# SCH_Sentinel-Controller-board_2025-03-25.net
KiCad netlist of a schematic drawn in EasyEDA
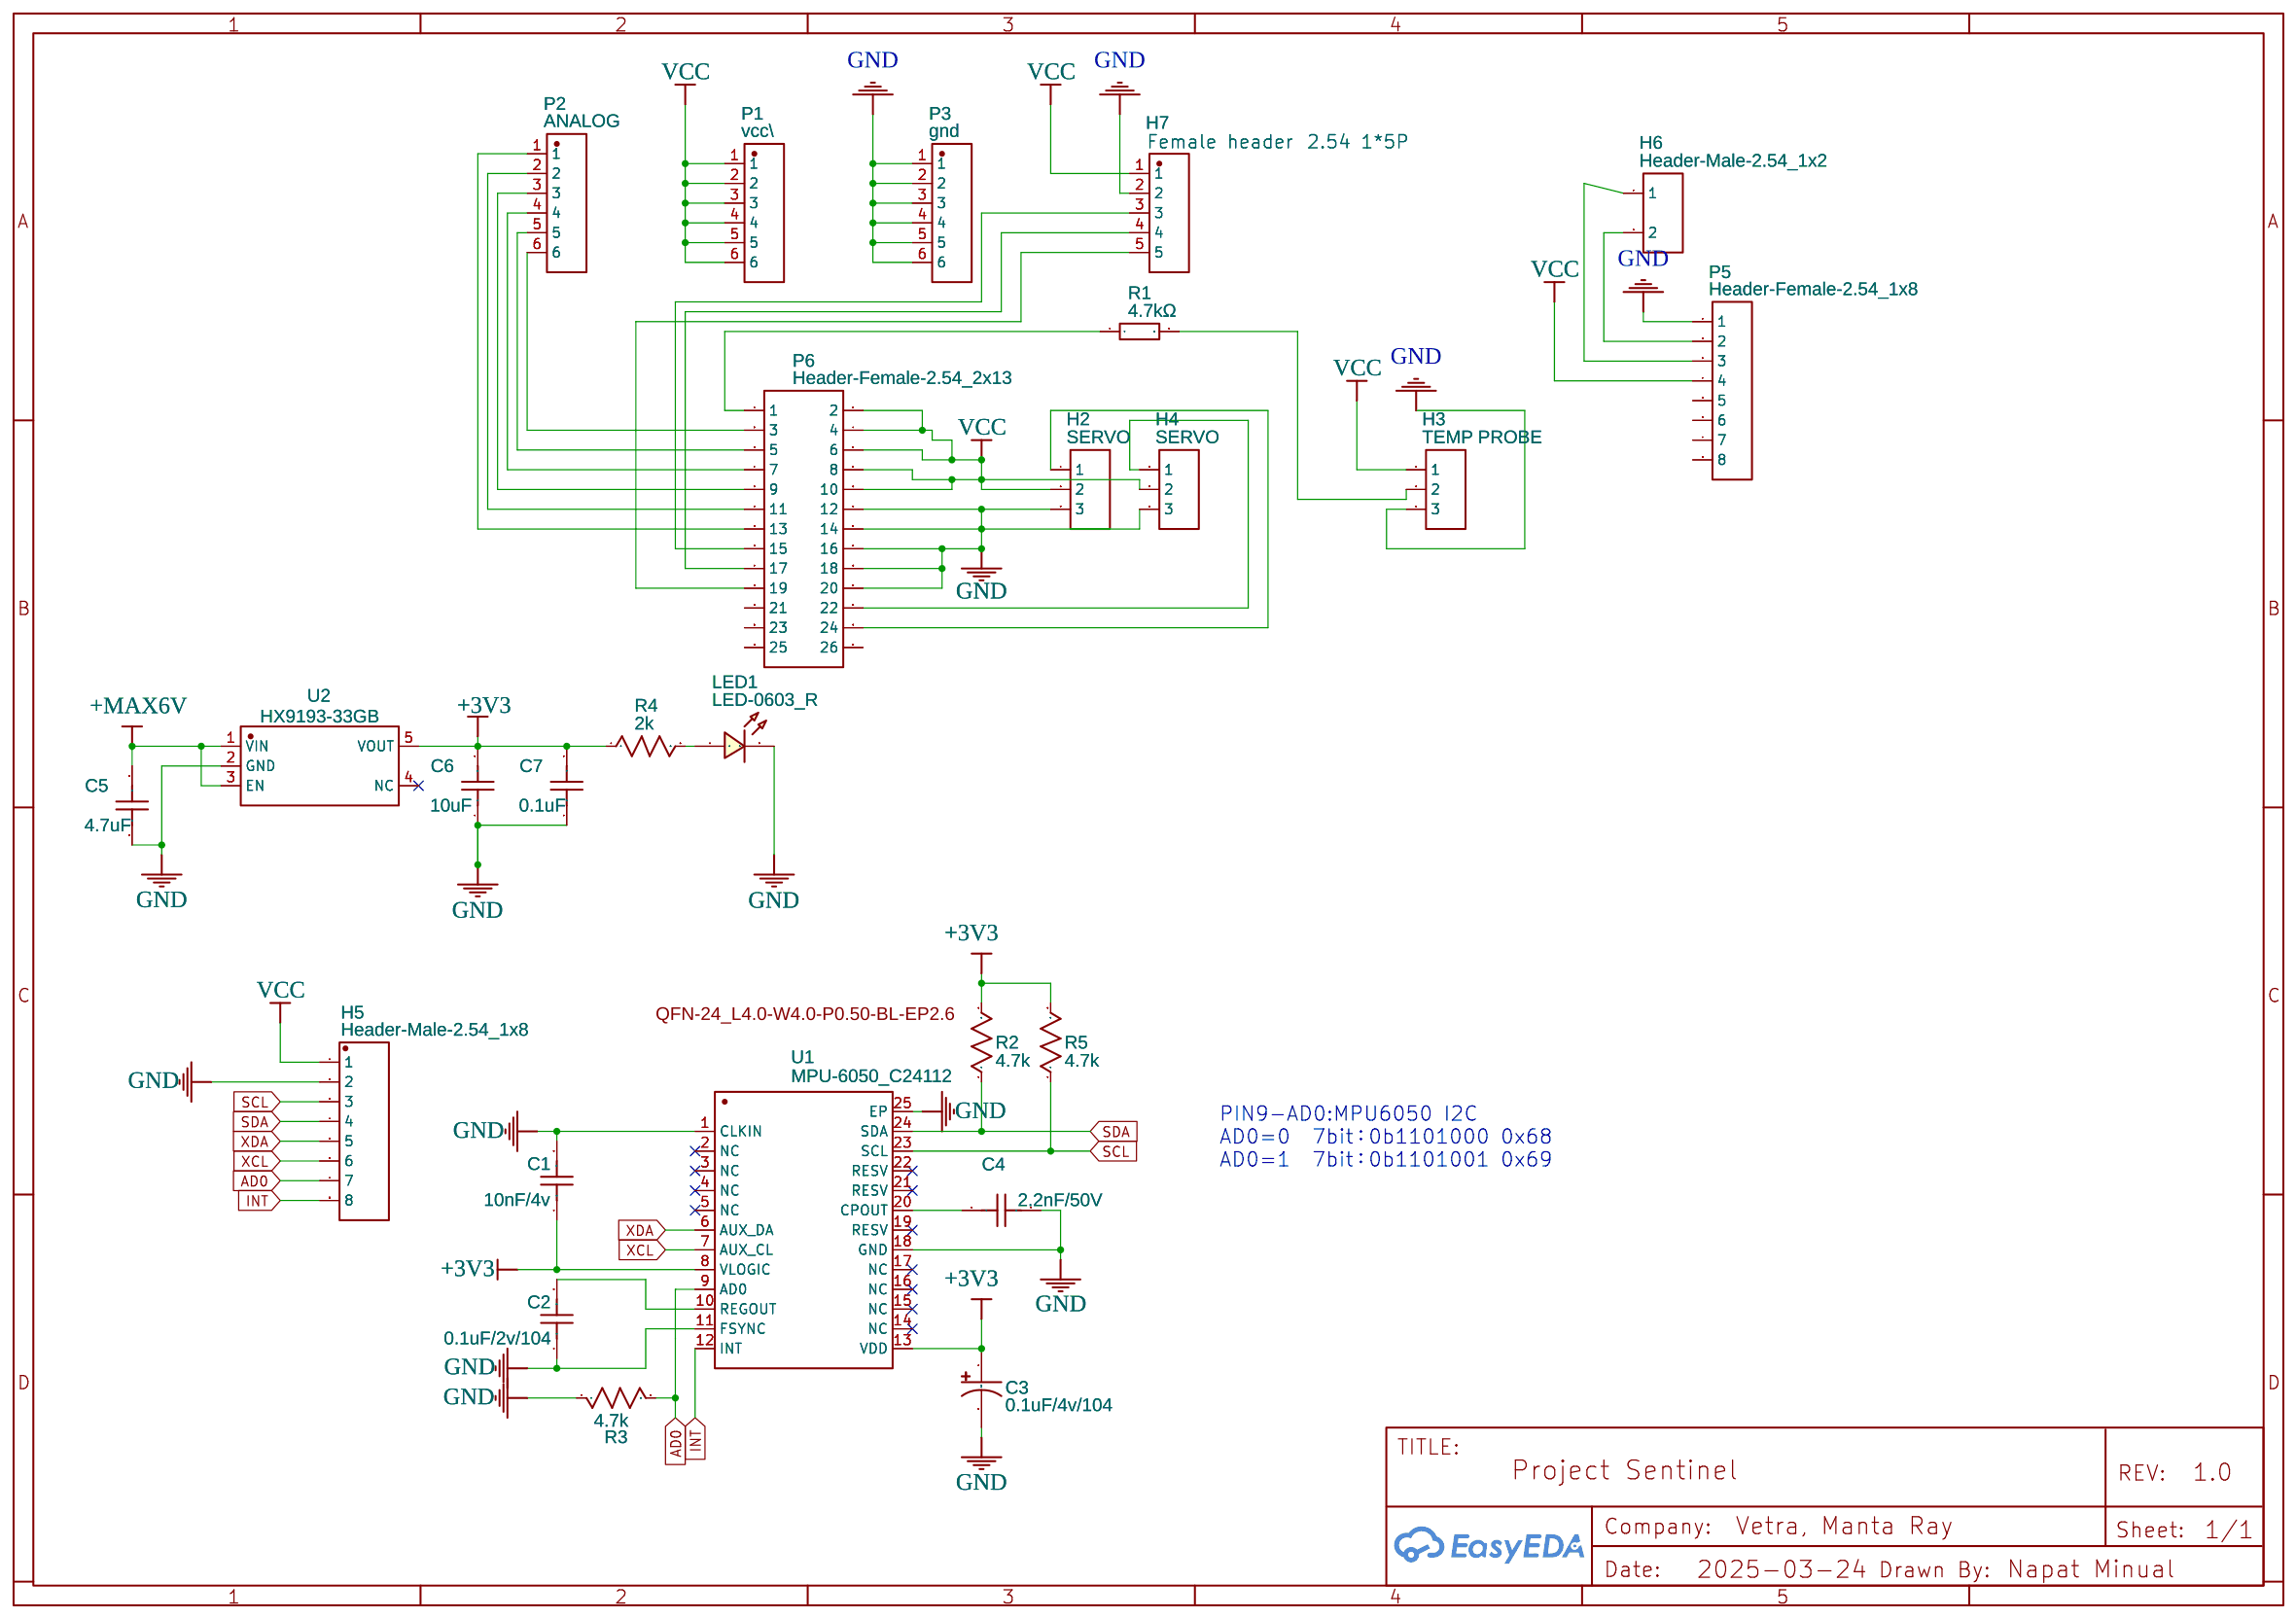
[diagram p0: schematic sheet]

(export (version "E")
  (design (tool "Eeschema 10.0.6"))
  (components
    (comp (ref "C1") (value "10nF/4v") (libsource (lib "") (part "C_0603_US")))
    (comp (ref "C2") (value "0.1uF/2v/104") (libsource (lib "") (part "C_0603_US")))
    (comp (ref "C3")
      (value "0.1uF/4v/104")
      (fields (field (name "Manufacturer Part") "TPSA106K016R1000") (field (name "Manufacturer") "AVX"))
      (libsource (lib "") (part "TPSA106K016R1000_C282116"))
    )
    (comp (ref "C4") (value "2.2nF/50V") (libsource (lib "") (part "C_0603_US_1")))
    (comp (ref "C5") (value "4.7uF") (libsource (lib "") (part "C_0603_US")))
    (comp (ref "C6") (value "10uF") (libsource (lib "") (part "C_0603_US")))
    (comp (ref "C7") (value "0.1uF") (libsource (lib "") (part "C_0603_US")))
    (comp (ref "H2")
      (value "SERVO")
      (fields (field (name "Manufacturer Part") "2.54-1*3P针") (field (name "Manufacturer") "BOOMELE(博穆精密)"))
      (libsource (lib "") (part "Header-Male-2.54_1x3"))
    )
    (comp (ref "H3")
      (value "TEMP PROBE")
      (fields (field (name "Manufacturer Part") "2.54-1*3P针") (field (name "Manufacturer") "BOOMELE(博穆精密)"))
      (libsource (lib "") (part "Header-Male-2.54_1x3"))
    )
    (comp (ref "H4")
      (value "SERVO")
      (fields (field (name "Manufacturer Part") "2.54-1*3P针") (field (name "Manufacturer") "BOOMELE(博穆精密)"))
      (libsource (lib "") (part "Header-Male-2.54_1x3"))
    )
    (comp (ref "H5")
      (value "Header-Male-2.54_1x8")
      (fields (field (name "Manufacturer Part") "B-2100S08P-A110") (field (name "Manufacturer") "Ckmtw(灿科盟)"))
      (libsource (lib "") (part "Header-Male-2.54_1x8"))
    )
    (comp (ref "H6")
      (value "Header-Male-2.54_1x2")
      (fields
        (field (name "Manufacturer Part") "826629-2")
        (field (name "Manufacturer") "TE Connectivity(泰科电子)")
      )
      (libsource (lib "") (part "Header-Male-2.54_1x2"))
    )
    (comp (ref "H7")
      (value "Female header　2.54 1*5Ｐ")
      (fields (field (name "Manufacturer Part") "排母　2.54 1*5Ｐ"))
      (libsource (lib "") (part "Female header　2.54 1*5Ｐ"))
    )
    (comp (ref "LED1")
      (value "LED-0603_R")
      (fields
        (field (name "Manufacturer Part") "19-217/R6C-AL1M2VY/3T")
        (field (name "Manufacturer") "EVERLIGHT(台湾亿光)")
      )
      (libsource (lib "") (part "LED-0603_R"))
    )
    (comp (ref "P1")
      (value "vcc\\")
      (fields (field (name "Manufacturer Part") "2.54-1*6P母") (field (name "Manufacturer") "BOOMELE(博穆精密)"))
      (libsource (lib "") (part "Header-Female-2.54_1x6"))
    )
    (comp (ref "P2")
      (value "ANALOG")
      (fields (field (name "Manufacturer Part") "2.54-1*6P母") (field (name "Manufacturer") "BOOMELE(博穆精密)"))
      (libsource (lib "") (part "Header-Female-2.54_1x6"))
    )
    (comp (ref "P3")
      (value "gnd")
      (fields (field (name "Manufacturer Part") "2.54-1*6P母") (field (name "Manufacturer") "BOOMELE(博穆精密)"))
      (libsource (lib "") (part "Header-Female-2.54_1x6"))
    )
    (comp (ref "P5")
      (value "Header-Female-2.54_1x8")
      (fields (field (name "Manufacturer Part") "2.54-1*8P母环保") (field (name "Manufacturer") "BOOMELE(博穆精密)"))
      (libsource (lib "") (part "Header-Female-2.54_1x8"))
    )
    (comp (ref "P6")
      (value "Header-Female-2.54_2x13")
      (fields (field (name "Manufacturer Part") "2.54-2*13P母") (field (name "Manufacturer") "BOOMELE(博穆精密)"))
      (libsource (lib "") (part "Header-Female-2.54_2x13"))
    )
    (comp (ref "R1")
      (value "4.7kΩ")
      (fields (field (name "Manufacturer Part") "RMC20104.7K1%N") (field (name "Manufacturer") "Tyohm(幸亚电阻)"))
      (libsource (lib "") (part "RMC20104.7K1%N"))
    )
    (comp (ref "R2") (value "4.7k") (libsource (lib "") (part "R_0603_US_2")))
    (comp (ref "R3") (value "4.7k") (libsource (lib "") (part "R_0603_US")))
    (comp (ref "R4") (value "2k") (libsource (lib "") (part "R_0603_US_1")))
    (comp (ref "R5") (value "4.7k") (libsource (lib "") (part "R_0603_US_2")))
    (comp (ref "U1")
      (value "MPU-6050_C24112")
      (fields (field (name "Manufacturer Part") "MPU-6050") (field (name "Manufacturer") "InvenSense"))
      (libsource (lib "") (part "MPU-6050_C24112"))
    )
    (comp (ref "U2")
      (value "HX9193-33GB")
      (fields (field (name "Manufacturer") "hengjiaxing"))
      (libsource (lib "") (part "HX9193-33GB"))
    )
  )
  (nets
    (net (code "1") (name "+3V3") (class "Default")
      (node (ref "C1") (pin "1") (pinfunction "1_1") (pintype "unspecified"))
      (node (ref "C3") (pin "1") (pinfunction "1_1") (pintype "unspecified"))
      (node (ref "C6") (pin "2") (pinfunction "2_2") (pintype "unspecified"))
      (node (ref "C7") (pin "2") (pinfunction "2_2") (pintype "unspecified"))
      (node (ref "R2") (pin "2") (pinfunction "2_2") (pintype "unspecified"))
      (node (ref "R4") (pin "1") (pinfunction "1_1") (pintype "unspecified"))
      (node (ref "R5") (pin "2") (pinfunction "2_2") (pintype "unspecified"))
      (node (ref "U1") (pin "13") (pinfunction "VDD_13") (pintype "unspecified"))
      (node (ref "U1") (pin "8") (pinfunction "VLOGIC_8") (pintype "unspecified"))
      (node (ref "U2") (pin "5") (pinfunction "VOUT_5") (pintype "unspecified"))
    )
    (net (code "2") (name "+MAX6V") (class "Default")
      (node (ref "C5") (pin "2") (pinfunction "2_2") (pintype "unspecified"))
      (node (ref "U2") (pin "1") (pinfunction "VIN_1") (pintype "unspecified"))
      (node (ref "U2") (pin "3") (pinfunction "EN_3") (pintype "unspecified"))
    )
    (net (code "3") (name "AD0") (class "Default")
      (node (ref "H5") (pin "7") (pinfunction "7_7") (pintype "unspecified"))
      (node (ref "R3") (pin "2") (pinfunction "2_2") (pintype "unspecified"))
      (node (ref "U1") (pin "9") (pinfunction "AD0_9") (pintype "unspecified"))
    )
    (net (code "4") (name "GND") (class "Default")
      (node (ref "C1") (pin "2") (pinfunction "2_2") (pintype "unspecified"))
      (node (ref "C2") (pin "1") (pinfunction "1_1") (pintype "unspecified"))
      (node (ref "C3") (pin "2") (pinfunction "2_2") (pintype "unspecified"))
      (node (ref "C4") (pin "1") (pinfunction "1_1") (pintype "unspecified"))
      (node (ref "C5") (pin "1") (pinfunction "1_1") (pintype "unspecified"))
      (node (ref "C6") (pin "1") (pinfunction "1_1") (pintype "unspecified"))
      (node (ref "C7") (pin "1") (pinfunction "1_1") (pintype "unspecified"))
      (node (ref "H2") (pin "3") (pinfunction "3_3") (pintype "input"))
      (node (ref "H3") (pin "3") (pinfunction "3_3") (pintype "input"))
      (node (ref "H4") (pin "3") (pinfunction "3_3") (pintype "input"))
      (node (ref "H5") (pin "2") (pinfunction "2_2") (pintype "unspecified"))
      (node (ref "H7") (pin "2") (pinfunction "2_2") (pintype "unspecified"))
      (node (ref "LED1") (pin "2") (pinfunction "2_2") (pintype "unspecified"))
      (node (ref "P3") (pin "1") (pinfunction "1_1") (pintype "unspecified"))
      (node (ref "P3") (pin "2") (pinfunction "2_2") (pintype "unspecified"))
      (node (ref "P3") (pin "3") (pinfunction "3_3") (pintype "unspecified"))
      (node (ref "P3") (pin "4") (pinfunction "4_4") (pintype "unspecified"))
      (node (ref "P3") (pin "5") (pinfunction "5_5") (pintype "unspecified"))
      (node (ref "P3") (pin "6") (pinfunction "6_6") (pintype "unspecified"))
      (node (ref "P5") (pin "1") (pinfunction "1_1") (pintype "input"))
      (node (ref "P6") (pin "12") (pinfunction "12_12") (pintype "input"))
      (node (ref "P6") (pin "14") (pinfunction "14_14") (pintype "input"))
      (node (ref "P6") (pin "16") (pinfunction "16_16") (pintype "input"))
      (node (ref "P6") (pin "18") (pinfunction "18_18") (pintype "input"))
      (node (ref "P6") (pin "20") (pinfunction "20_20") (pintype "input"))
      (node (ref "R3") (pin "1") (pinfunction "1_1") (pintype "unspecified"))
      (node (ref "U1") (pin "1") (pinfunction "CLKIN_1") (pintype "unspecified"))
      (node (ref "U1") (pin "11") (pinfunction "FSYNC_11") (pintype "unspecified"))
      (node (ref "U1") (pin "18") (pinfunction "GND_18") (pintype "unspecified"))
      (node (ref "U1") (pin "25") (pinfunction "EP_25") (pintype "unspecified"))
      (node (ref "U2") (pin "2") (pinfunction "GND_2") (pintype "unspecified"))
    )
    (net (code "5") (name "INT") (class "Default")
      (node (ref "H5") (pin "8") (pinfunction "8_8") (pintype "unspecified"))
      (node (ref "U1") (pin "12") (pinfunction "INT_12") (pintype "unspecified"))
    )
    (net (code "6") (name "Net-(H2-Pad1)") (class "Default")
      (node (ref "H2") (pin "1") (pinfunction "1_1") (pintype "input"))
      (node (ref "P6") (pin "24") (pinfunction "24_24") (pintype "input"))
    )
    (net (code "7") (name "Net-(H3-Pad2)") (class "Default")
      (node (ref "H3") (pin "2") (pinfunction "2_2") (pintype "input"))
      (node (ref "R1") (pin "2") (pinfunction "2_2") (pintype "unspecified"))
    )
    (net (code "8") (name "Net-(H4-Pad1)") (class "Default")
      (node (ref "H4") (pin "1") (pinfunction "1_1") (pintype "input"))
      (node (ref "P6") (pin "22") (pinfunction "22_22") (pintype "input"))
    )
    (net (code "9") (name "Net-(H6-Pad1)") (class "Default")
      (node (ref "H6") (pin "1") (pinfunction "1_1") (pintype "unspecified"))
      (node (ref "P5") (pin "3") (pinfunction "3_3") (pintype "input"))
    )
    (net (code "10") (name "Net-(H6-Pad2)") (class "Default")
      (node (ref "H6") (pin "2") (pinfunction "2_2") (pintype "unspecified"))
      (node (ref "P5") (pin "2") (pinfunction "2_2") (pintype "input"))
    )
    (net (code "11") (name "Net-(H7-Pad3)") (class "Default")
      (node (ref "H7") (pin "3") (pinfunction "3_3") (pintype "unspecified"))
      (node (ref "P6") (pin "15") (pinfunction "15_15") (pintype "input"))
    )
    (net (code "12") (name "Net-(H7-Pad4)") (class "Default")
      (node (ref "H7") (pin "4") (pinfunction "4_4") (pintype "unspecified"))
      (node (ref "P6") (pin "17") (pinfunction "17_17") (pintype "input"))
    )
    (net (code "13") (name "Net-(H7-Pad5)") (class "Default")
      (node (ref "H7") (pin "5") (pinfunction "5_5") (pintype "unspecified"))
      (node (ref "P6") (pin "19") (pinfunction "19_19") (pintype "input"))
    )
    (net (code "14") (name "Net-(LED1-Pad1)") (class "Default")
      (node (ref "LED1") (pin "1") (pinfunction "1_1") (pintype "unspecified"))
      (node (ref "R4") (pin "2") (pinfunction "2_2") (pintype "unspecified"))
    )
    (net (code "15") (name "Net-(P2-Pad1)") (class "Default")
      (node (ref "P2") (pin "1") (pinfunction "1_1") (pintype "unspecified"))
      (node (ref "P6") (pin "13") (pinfunction "13_13") (pintype "input"))
    )
    (net (code "16") (name "Net-(P2-Pad2)") (class "Default")
      (node (ref "P2") (pin "2") (pinfunction "2_2") (pintype "unspecified"))
      (node (ref "P6") (pin "11") (pinfunction "11_11") (pintype "input"))
    )
    (net (code "17") (name "Net-(P2-Pad3)") (class "Default")
      (node (ref "P2") (pin "3") (pinfunction "3_3") (pintype "unspecified"))
      (node (ref "P6") (pin "9") (pinfunction "9_9") (pintype "input"))
    )
    (net (code "18") (name "Net-(P2-Pad4)") (class "Default")
      (node (ref "P2") (pin "4") (pinfunction "4_4") (pintype "unspecified"))
      (node (ref "P6") (pin "7") (pinfunction "7_7") (pintype "input"))
    )
    (net (code "19") (name "Net-(P2-Pad5)") (class "Default")
      (node (ref "P2") (pin "5") (pinfunction "5_5") (pintype "unspecified"))
      (node (ref "P6") (pin "5") (pinfunction "5_5") (pintype "input"))
    )
    (net (code "20") (name "Net-(P2-Pad6)") (class "Default")
      (node (ref "P2") (pin "6") (pinfunction "6_6") (pintype "unspecified"))
      (node (ref "P6") (pin "3") (pinfunction "3_3") (pintype "input"))
    )
    (net (code "21") (name "Net-(P6-Pad1)") (class "Default")
      (node (ref "P6") (pin "1") (pinfunction "1_1") (pintype "input"))
      (node (ref "R1") (pin "1") (pinfunction "1_1") (pintype "unspecified"))
    )
    (net (code "22") (name "Net-(U1-CPOUT)") (class "Default")
      (node (ref "C4") (pin "2") (pinfunction "2_2") (pintype "unspecified"))
      (node (ref "U1") (pin "20") (pinfunction "CPOUT_20") (pintype "unspecified"))
    )
    (net (code "23") (name "Net-(U1-REGOUT)") (class "Default")
      (node (ref "C2") (pin "2") (pinfunction "2_2") (pintype "unspecified"))
      (node (ref "U1") (pin "10") (pinfunction "REGOUT_10") (pintype "unspecified"))
    )
    (net (code "24") (name "SCL") (class "Default")
      (node (ref "H5") (pin "3") (pinfunction "3_3") (pintype "unspecified"))
      (node (ref "R5") (pin "1") (pinfunction "1_1") (pintype "unspecified"))
      (node (ref "U1") (pin "23") (pinfunction "SCL_23") (pintype "unspecified"))
    )
    (net (code "25") (name "SDA") (class "Default")
      (node (ref "H5") (pin "4") (pinfunction "4_4") (pintype "unspecified"))
      (node (ref "R2") (pin "1") (pinfunction "1_1") (pintype "unspecified"))
      (node (ref "U1") (pin "24") (pinfunction "SDA_24") (pintype "unspecified"))
    )
    (net (code "26") (name "VCC") (class "Default")
      (node (ref "H2") (pin "2") (pinfunction "2_2") (pintype "input"))
      (node (ref "H3") (pin "1") (pinfunction "1_1") (pintype "input"))
      (node (ref "H4") (pin "2") (pinfunction "2_2") (pintype "input"))
      (node (ref "H5") (pin "1") (pinfunction "1_1") (pintype "unspecified"))
      (node (ref "H7") (pin "1") (pinfunction "1_1") (pintype "unspecified"))
      (node (ref "P1") (pin "1") (pinfunction "1_1") (pintype "unspecified"))
      (node (ref "P1") (pin "2") (pinfunction "2_2") (pintype "unspecified"))
      (node (ref "P1") (pin "3") (pinfunction "3_3") (pintype "unspecified"))
      (node (ref "P1") (pin "4") (pinfunction "4_4") (pintype "unspecified"))
      (node (ref "P1") (pin "5") (pinfunction "5_5") (pintype "unspecified"))
      (node (ref "P1") (pin "6") (pinfunction "6_6") (pintype "unspecified"))
      (node (ref "P5") (pin "4") (pinfunction "4_4") (pintype "input"))
      (node (ref "P6") (pin "10") (pinfunction "10_10") (pintype "input"))
      (node (ref "P6") (pin "2") (pinfunction "2_2") (pintype "input"))
      (node (ref "P6") (pin "4") (pinfunction "4_4") (pintype "input"))
      (node (ref "P6") (pin "6") (pinfunction "6_6") (pintype "input"))
      (node (ref "P6") (pin "8") (pinfunction "8_8") (pintype "input"))
    )
    (net (code "27") (name "XCL") (class "Default")
      (node (ref "H5") (pin "6") (pinfunction "6_6") (pintype "unspecified"))
      (node (ref "U1") (pin "7") (pinfunction "AUX_CL_7") (pintype "unspecified"))
    )
    (net (code "28") (name "XDA") (class "Default")
      (node (ref "H5") (pin "5") (pinfunction "5_5") (pintype "unspecified"))
      (node (ref "U1") (pin "6") (pinfunction "AUX_DA_6") (pintype "unspecified"))
    )
    (net (code "29") (name "unconnected-(P5-Pad5)") (class "Default")
      (node (ref "P5") (pin "5") (pinfunction "5_5") (pintype "input"))
    )
    (net (code "30") (name "unconnected-(P5-Pad6)") (class "Default")
      (node (ref "P5") (pin "6") (pinfunction "6_6") (pintype "input"))
    )
    (net (code "31") (name "unconnected-(P5-Pad7)") (class "Default")
      (node (ref "P5") (pin "7") (pinfunction "7_7") (pintype "input"))
    )
    (net (code "32") (name "unconnected-(P5-Pad8)") (class "Default")
      (node (ref "P5") (pin "8") (pinfunction "8_8") (pintype "input"))
    )
    (net (code "33") (name "unconnected-(P6-Pad21)") (class "Default")
      (node (ref "P6") (pin "21") (pinfunction "21_21") (pintype "input"))
    )
    (net (code "34") (name "unconnected-(P6-Pad23)") (class "Default")
      (node (ref "P6") (pin "23") (pinfunction "23_23") (pintype "input"))
    )
    (net (code "35") (name "unconnected-(P6-Pad25)") (class "Default")
      (node (ref "P6") (pin "25") (pinfunction "25_25") (pintype "input"))
    )
    (net (code "36") (name "unconnected-(P6-Pad26)") (class "Default")
      (node (ref "P6") (pin "26") (pinfunction "26_26") (pintype "input"))
    )
    (net (code "37") (name "unconnected-(U1-NC-Pad2)") (class "Default")
      (node (ref "U1") (pin "2") (pinfunction "NC_2") (pintype "unspecified+no_connect"))
    )
    (net (code "38") (name "unconnected-(U1-NC-Pad3)") (class "Default")
      (node (ref "U1") (pin "3") (pinfunction "NC_3") (pintype "unspecified+no_connect"))
    )
    (net (code "39") (name "unconnected-(U1-NC-Pad4)") (class "Default")
      (node (ref "U1") (pin "4") (pinfunction "NC_4") (pintype "unspecified+no_connect"))
    )
    (net (code "40") (name "unconnected-(U1-NC-Pad5)") (class "Default")
      (node (ref "U1") (pin "5") (pinfunction "NC_5") (pintype "unspecified+no_connect"))
    )
    (net (code "41") (name "unconnected-(U1-NC-Pad14)") (class "Default")
      (node (ref "U1") (pin "14") (pinfunction "NC_14") (pintype "unspecified+no_connect"))
    )
    (net (code "42") (name "unconnected-(U1-NC-Pad15)") (class "Default")
      (node (ref "U1") (pin "15") (pinfunction "NC_15") (pintype "unspecified+no_connect"))
    )
    (net (code "43") (name "unconnected-(U1-NC-Pad16)") (class "Default")
      (node (ref "U1") (pin "16") (pinfunction "NC_16") (pintype "unspecified+no_connect"))
    )
    (net (code "44") (name "unconnected-(U1-NC-Pad17)") (class "Default")
      (node (ref "U1") (pin "17") (pinfunction "NC_17") (pintype "unspecified+no_connect"))
    )
    (net (code "45") (name "unconnected-(U1-RESV-Pad19)") (class "Default")
      (node (ref "U1") (pin "19") (pinfunction "RESV_19") (pintype "unspecified+no_connect"))
    )
    (net (code "46") (name "unconnected-(U1-RESV-Pad21)") (class "Default")
      (node (ref "U1") (pin "21") (pinfunction "RESV_21") (pintype "unspecified+no_connect"))
    )
    (net (code "47") (name "unconnected-(U1-RESV-Pad22)") (class "Default")
      (node (ref "U1") (pin "22") (pinfunction "RESV_22") (pintype "unspecified+no_connect"))
    )
    (net (code "48") (name "unconnected-(U2-NC-Pad4)") (class "Default")
      (node (ref "U2") (pin "4") (pinfunction "NC_4") (pintype "unspecified+no_connect"))
    )
  )
)
